# LMT70.net
KiCad netlist of a schematic drawn in EAGLE
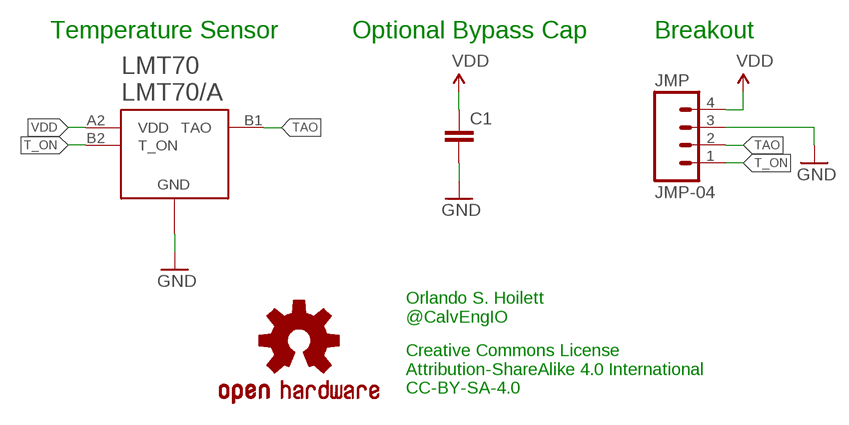
[diagram p0: schematic, sheet 1]

(export (version "E")
  (design (tool "Eeschema 10.0.6"))
  (components
    (comp (ref "C1")
      (value "C-EUC0402")
      (footprint "eagle-import:C0402")
      (libsource (lib "eagle-import") (part "C-EUC0402"))
    )
    (comp (ref "JMP")
      (value "JMP-04")
      (footprint "eagle-import:JMP-04")
      (libsource (lib "eagle-import") (part "JMP-04"))
    )
    (comp (ref "LMT70")
      (value "LMT70/A")
      (footprint "eagle-import:4-DSBGA")
      (libsource (lib "eagle-import") (part "LMT70/A"))
    )
    (comp (ref "LOGO1")
      (value "OSHW-LOGOM")
      (footprint "eagle-import:OSHW-LOGO-M")
      (libsource (lib "eagle-import") (part "OSHW-LOGOM"))
    )
  )
  (nets
    (net (code "1") (name "GND") (class "Default")
      (node (ref "C1") (pin "2") (pinfunction "2_2") (pintype "passive"))
      (node (ref "JMP") (pin "3") (pinfunction "3_3") (pintype "passive"))
      (node (ref "LMT70") (pin "A1") (pinfunction "GND_A1") (pintype "bidirectional"))
    )
    (net (code "2") (name "TAO") (class "Default")
      (node (ref "JMP") (pin "2") (pinfunction "2_2") (pintype "passive"))
      (node (ref "LMT70") (pin "B1") (pinfunction "TAO_B1") (pintype "bidirectional"))
    )
    (net (code "3") (name "T_ON") (class "Default")
      (node (ref "JMP") (pin "1") (pinfunction "1_1") (pintype "passive"))
      (node (ref "LMT70") (pin "B2") (pinfunction "T_ON_B2") (pintype "bidirectional"))
    )
    (net (code "4") (name "VDD") (class "Default")
      (node (ref "C1") (pin "1") (pinfunction "1_1") (pintype "passive"))
      (node (ref "JMP") (pin "4") (pinfunction "4_4") (pintype "passive"))
      (node (ref "LMT70") (pin "A2") (pinfunction "VDD_A2") (pintype "bidirectional"))
    )
  )
)
